# SLAYER_Storage.net
KiCad netlist of a schematic drawn in Altium Designer
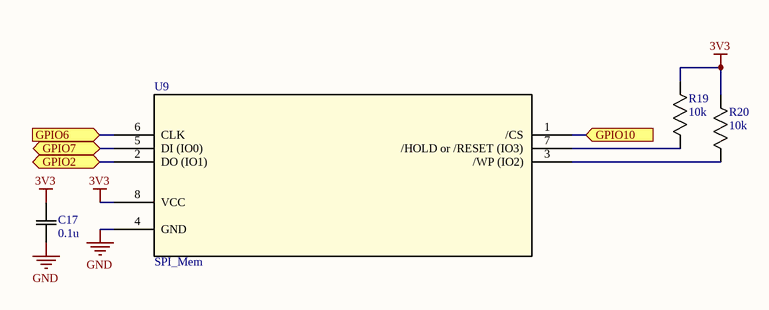
[diagram p0: SLAYER_Storage.SchDoc]

(export (version "E")
  (design (tool "Eeschema 10.0.6"))
  (components
    (comp (ref "C17")
      (value "0.1u")
      (footprint "0.1uF/50V")
      (description "CC0603KRX7R9BB104")
      (fields (field (name "COPYRIGHT") "Copyright (C) 2025 Ultra Librarian. All rights reserved."))
      (libsource (lib "SLAYER_Altium_Sch") (part "0.1uF/50V"))
    )
    (comp (ref "R19")
      (value "10k")
      (footprint "10k/0.125W")
      (description "CRCW060310K0FKEA")
      (fields (field (name "COPYRIGHT") "Copyright (C) 2025 Ultra Librarian. All rights reserved."))
      (libsource (lib "SLAYER_Altium_Sch") (part "10k/0.125W"))
    )
    (comp (ref "R20")
      (value "10k")
      (footprint "10k/0.125W")
      (description "CRCW060310K0FKEA")
      (fields (field (name "COPYRIGHT") "Copyright (C) 2025 Ultra Librarian. All rights reserved."))
      (libsource (lib "SLAYER_Altium_Sch") (part "10k/0.125W"))
    )
    (comp (ref "U9")
      (value "SPI_Mem")
      (footprint "SPI_Memory/1Mb")
      (description "W25Q128JVSIQ")
      (fields (field (name "COPYRIGHT") "Copyright (C) 2026 Ultra Librarian. All rights reserved."))
      (libsource (lib "SLAYER_Altium_Sch") (part "SPI_Memory/1Mb"))
    )
  )
  (nets
    (net (code "1") (name "/GPIO2") (class "Default")
      (node (ref "U9") (pin "2") (pinfunction "DO_(IO1)_2") (pintype "passive"))
    )
    (net (code "2") (name "/GPIO6") (class "Default")
      (node (ref "U9") (pin "6") (pinfunction "CLK_6") (pintype "passive"))
    )
    (net (code "3") (name "/GPIO7") (class "Default")
      (node (ref "U9") (pin "5") (pinfunction "DI_(IO0)_5") (pintype "passive"))
    )
    (net (code "4") (name "/GPIO10") (class "Default")
      (node (ref "U9") (pin "1") (pinfunction "/CS_1") (pintype "passive"))
    )
    (net (code "5") (name "3V3") (class "Default")
      (node (ref "C17") (pin "2") (pinfunction "2_2") (pintype "passive"))
      (node (ref "R19") (pin "1") (pinfunction "1_1") (pintype "passive"))
      (node (ref "R20") (pin "1") (pinfunction "1_1") (pintype "passive"))
      (node (ref "U9") (pin "8") (pinfunction "VCC_8") (pintype "power_in"))
    )
    (net (code "6") (name "GND") (class "Default")
      (node (ref "C17") (pin "1") (pinfunction "1_1") (pintype "passive"))
      (node (ref "U9") (pin "4") (pinfunction "GND_4") (pintype "power_in"))
    )
    (net (code "7") (name "Net-(U9-{slash}HOLD_or_{slash}RESET_(IO3))") (class "Default")
      (node (ref "R19") (pin "2") (pinfunction "2_2") (pintype "passive"))
      (node (ref "U9") (pin "7") (pinfunction "/HOLD_or_/RESET_(IO3)_7") (pintype "passive"))
    )
    (net (code "8") (name "Net-(U9-{slash}WP_(IO2))") (class "Default")
      (node (ref "R20") (pin "2") (pinfunction "2_2") (pintype "passive"))
      (node (ref "U9") (pin "3") (pinfunction "/WP_(IO2)_3") (pintype "passive"))
    )
  )
)
